# Headphone.net
KiCad netlist of a schematic drawn in Altium Designer
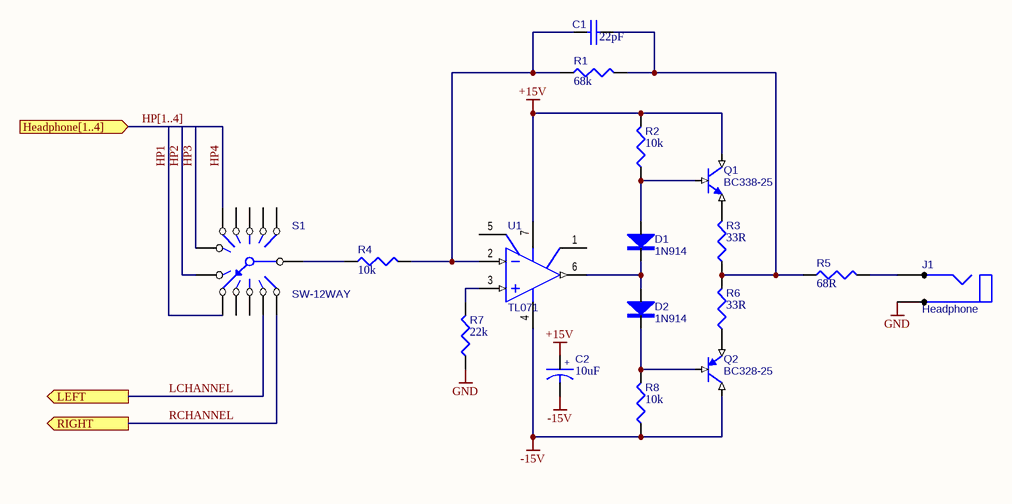
[diagram p0: Headphone.SchDoc]

(export (version "E")
  (design (tool "Eeschema 10.0.6"))
  (components
    (comp (ref "C1")
      (value "22pF")
      (footprint "RAD0.2")
      (description "Capacitor")
      (libsource (lib "*") (part "CAP"))
    )
    (comp (ref "C2")
      (value "10uF")
      (footprint "RB.2/.4")
      (description "Bi-Polar Capacitor")
      (libsource (lib "*") (part "CAPACITOR POL"))
    )
    (comp (ref "D1")
      (value "1N914")
      (footprint "DIODE0.4")
      (description "Diode")
      (libsource (lib "*") (part "1N914"))
    )
    (comp (ref "D2")
      (value "1N914")
      (footprint "DIODE0.4")
      (description "Diode")
      (libsource (lib "*") (part "1N914"))
    )
    (comp (ref "J1")
      (value "Headphone")
      (footprint "JACK-6.25MM")
      (libsource (lib "*") (part "PHONEJACK MONO"))
    )
    (comp (ref "Q1")
      (value "BC338-25")
      (footprint "TO-92A")
      (description "NPN BJT")
      (libsource (lib "*") (part "BC338-25"))
    )
    (comp (ref "Q2")
      (value "BC328-25")
      (footprint "TO-92A")
      (description "PNP BJT")
      (libsource (lib "*") (part "BC328-25"))
    )
    (comp (ref "R1")
      (value "68k")
      (footprint "AXIAL0.4")
      (description "Resistor")
      (libsource (lib "*") (part "RES1"))
    )
    (comp (ref "R2")
      (value "10k")
      (footprint "AXIAL0.4")
      (description "Resistor")
      (libsource (lib "") (part "RES1_1"))
    )
    (comp (ref "R3")
      (value "33R")
      (footprint "AXIAL0.4")
      (description "Resistor")
      (libsource (lib "") (part "RES1_1"))
    )
    (comp (ref "R4")
      (value "10k")
      (footprint "AXIAL0.4")
      (description "Resistor")
      (libsource (lib "*") (part "RES1"))
    )
    (comp (ref "R5")
      (value "68R")
      (footprint "AXIAL0.4")
      (description "Resistor")
      (libsource (lib "*") (part "RES1"))
    )
    (comp (ref "R6")
      (value "33R")
      (footprint "AXIAL0.4")
      (description "Resistor")
      (libsource (lib "") (part "RES1_1"))
    )
    (comp (ref "R7")
      (value "22k")
      (footprint "AXIAL0.4")
      (description "Resistor")
      (libsource (lib "") (part "RES1_1"))
    )
    (comp (ref "R8")
      (value "10k")
      (footprint "AXIAL0.4")
      (description "Resistor")
      (libsource (lib "") (part "RES1_1"))
    )
    (comp (ref "S1") (value "SW-12WAY") (footprint "SW-12WAY") (libsource (lib "*") (part "SW-12WAY")))
    (comp (ref "U1")
      (value "TL071")
      (footprint "DIP8")
      (description "Low-Noise  JFET-Input Operational Amplifiers")
      (libsource (lib "*") (part "TL071"))
    )
  )
  (nets
    (net (code "1") (name "+15V") (class "Default")
      (node (ref "C2") (pin "1") (pinfunction "1_1") (pintype "passive"))
      (node (ref "Q1") (pin "1") (pinfunction "C_1") (pintype "input"))
      (node (ref "R2") (pin "2") (pinfunction "2_2") (pintype "passive"))
      (node (ref "U1") (pin "7") (pinfunction "VCC+_7") (pintype "power_in"))
    )
    (net (code "2") (name "-15V") (class "Default")
      (node (ref "C2") (pin "2") (pinfunction "2_2") (pintype "passive"))
      (node (ref "Q2") (pin "1") (pinfunction "C_1") (pintype "input"))
      (node (ref "R8") (pin "1") (pinfunction "1_1") (pintype "passive"))
      (node (ref "U1") (pin "4") (pinfunction "VCC-_4") (pintype "power_in"))
    )
    (net (code "3") (name "/HP1") (class "Default")
      (node (ref "S1") (pin "8") (pinfunction "8_8") (pintype "passive"))
    )
    (net (code "4") (name "/HP2") (class "Default")
      (node (ref "S1") (pin "7") (pinfunction "7_7") (pintype "passive"))
    )
    (net (code "5") (name "/HP3") (class "Default")
      (node (ref "S1") (pin "6") (pinfunction "6_6") (pintype "passive"))
    )
    (net (code "6") (name "/HP4") (class "Default")
      (node (ref "S1") (pin "5") (pinfunction "5_5") (pintype "passive"))
    )
    (net (code "8") (name "/LCHANNEL") (class "Default")
      (node (ref "S1") (pin "11") (pinfunction "11_11") (pintype "passive"))
    )
    (net (code "9") (name "/RCHANNEL") (class "Default")
      (node (ref "S1") (pin "12") (pinfunction "12_12") (pintype "passive"))
    )
    (net (code "10") (name "GND") (class "Default")
      (node (ref "J1") (pin "3") (pinfunction "C_3") (pintype "passive"))
      (node (ref "R7") (pin "1") (pinfunction "1_1") (pintype "passive"))
    )
    (net (code "11") (name "Net-(C1-Pad2)") (class "Default")
      (node (ref "C1") (pin "2") (pinfunction "2_2") (pintype "passive"))
      (node (ref "R1") (pin "2") (pinfunction "2_2") (pintype "passive"))
      (node (ref "R3") (pin "1") (pinfunction "1_1") (pintype "passive"))
      (node (ref "R5") (pin "1") (pinfunction "1_1") (pintype "passive"))
      (node (ref "R6") (pin "2") (pinfunction "2_2") (pintype "passive"))
    )
    (net (code "12") (name "Net-(D1-A)") (class "Default")
      (node (ref "D1") (pin "1") (pinfunction "A_1") (pintype "passive"))
      (node (ref "Q1") (pin "2") (pinfunction "B_2") (pintype "input"))
      (node (ref "R2") (pin "1") (pinfunction "1_1") (pintype "passive"))
    )
    (net (code "13") (name "Net-(D1-K)") (class "Default")
      (node (ref "D1") (pin "2") (pinfunction "K_2") (pintype "passive"))
      (node (ref "D2") (pin "1") (pinfunction "A_1") (pintype "passive"))
      (node (ref "U1") (pin "6") (pinfunction "OUT_6") (pintype "output"))
    )
    (net (code "14") (name "Net-(D2-K)") (class "Default")
      (node (ref "D2") (pin "2") (pinfunction "K_2") (pintype "passive"))
      (node (ref "Q2") (pin "2") (pinfunction "B_2") (pintype "input"))
      (node (ref "R8") (pin "2") (pinfunction "2_2") (pintype "passive"))
    )
    (net (code "15") (name "Net-(J1-A)") (class "Default")
      (node (ref "J1") (pin "1") (pinfunction "A_1") (pintype "passive"))
      (node (ref "R5") (pin "2") (pinfunction "2_2") (pintype "passive"))
    )
    (net (code "16") (name "Net-(Q1-E)") (class "Default")
      (node (ref "Q1") (pin "3") (pinfunction "E_3") (pintype "input"))
      (node (ref "R3") (pin "2") (pinfunction "2_2") (pintype "passive"))
    )
    (net (code "17") (name "Net-(Q2-E)") (class "Default")
      (node (ref "Q2") (pin "3") (pinfunction "E_3") (pintype "input"))
      (node (ref "R6") (pin "1") (pinfunction "1_1") (pintype "passive"))
    )
    (net (code "18") (name "Net-(R4-Pad1)") (class "Default")
      (node (ref "R4") (pin "1") (pinfunction "1_1") (pintype "passive"))
      (node (ref "S1") (pin "13") (pinfunction "13_13") (pintype "passive"))
    )
    (net (code "19") (name "Net-(U1-IN+)") (class "Default")
      (node (ref "R7") (pin "2") (pinfunction "2_2") (pintype "passive"))
      (node (ref "U1") (pin "3") (pinfunction "IN+_3") (pintype "input"))
    )
    (net (code "20") (name "Net-(U1-IN-)") (class "Default")
      (node (ref "C1") (pin "1") (pinfunction "1_1") (pintype "passive"))
      (node (ref "R1") (pin "1") (pinfunction "1_1") (pintype "passive"))
      (node (ref "R4") (pin "2") (pinfunction "2_2") (pintype "passive"))
      (node (ref "U1") (pin "2") (pinfunction "IN-_2") (pintype "input"))
    )
    (net (code "21") (name "unconnected-(S1-Pad1)") (class "Default")
      (node (ref "S1") (pin "1") (pinfunction "1_1") (pintype "passive"))
    )
    (net (code "22") (name "unconnected-(S1-Pad2)") (class "Default")
      (node (ref "S1") (pin "2") (pinfunction "2_2") (pintype "passive"))
    )
    (net (code "23") (name "unconnected-(S1-Pad3)") (class "Default")
      (node (ref "S1") (pin "3") (pinfunction "3_3") (pintype "passive"))
    )
    (net (code "24") (name "unconnected-(S1-Pad4)") (class "Default")
      (node (ref "S1") (pin "4") (pinfunction "4_4") (pintype "passive"))
    )
    (net (code "25") (name "unconnected-(S1-Pad9)") (class "Default")
      (node (ref "S1") (pin "9") (pinfunction "9_9") (pintype "passive"))
    )
    (net (code "26") (name "unconnected-(S1-Pad10)") (class "Default")
      (node (ref "S1") (pin "10") (pinfunction "10_10") (pintype "passive"))
    )
    (net (code "27") (name "unconnected-(U1-N1{slash}O.S.-Pad1)") (class "Default")
      (node (ref "U1") (pin "1") (pinfunction "N1/O.S._1") (pintype "passive"))
    )
    (net (code "28") (name "unconnected-(U1-O.S._N2-Pad5)") (class "Default")
      (node (ref "U1") (pin "5") (pinfunction "O.S._N2_5") (pintype "passive"))
    )
  )
)
